# motordriver.net
KiCad netlist of a schematic drawn in Altium Designer
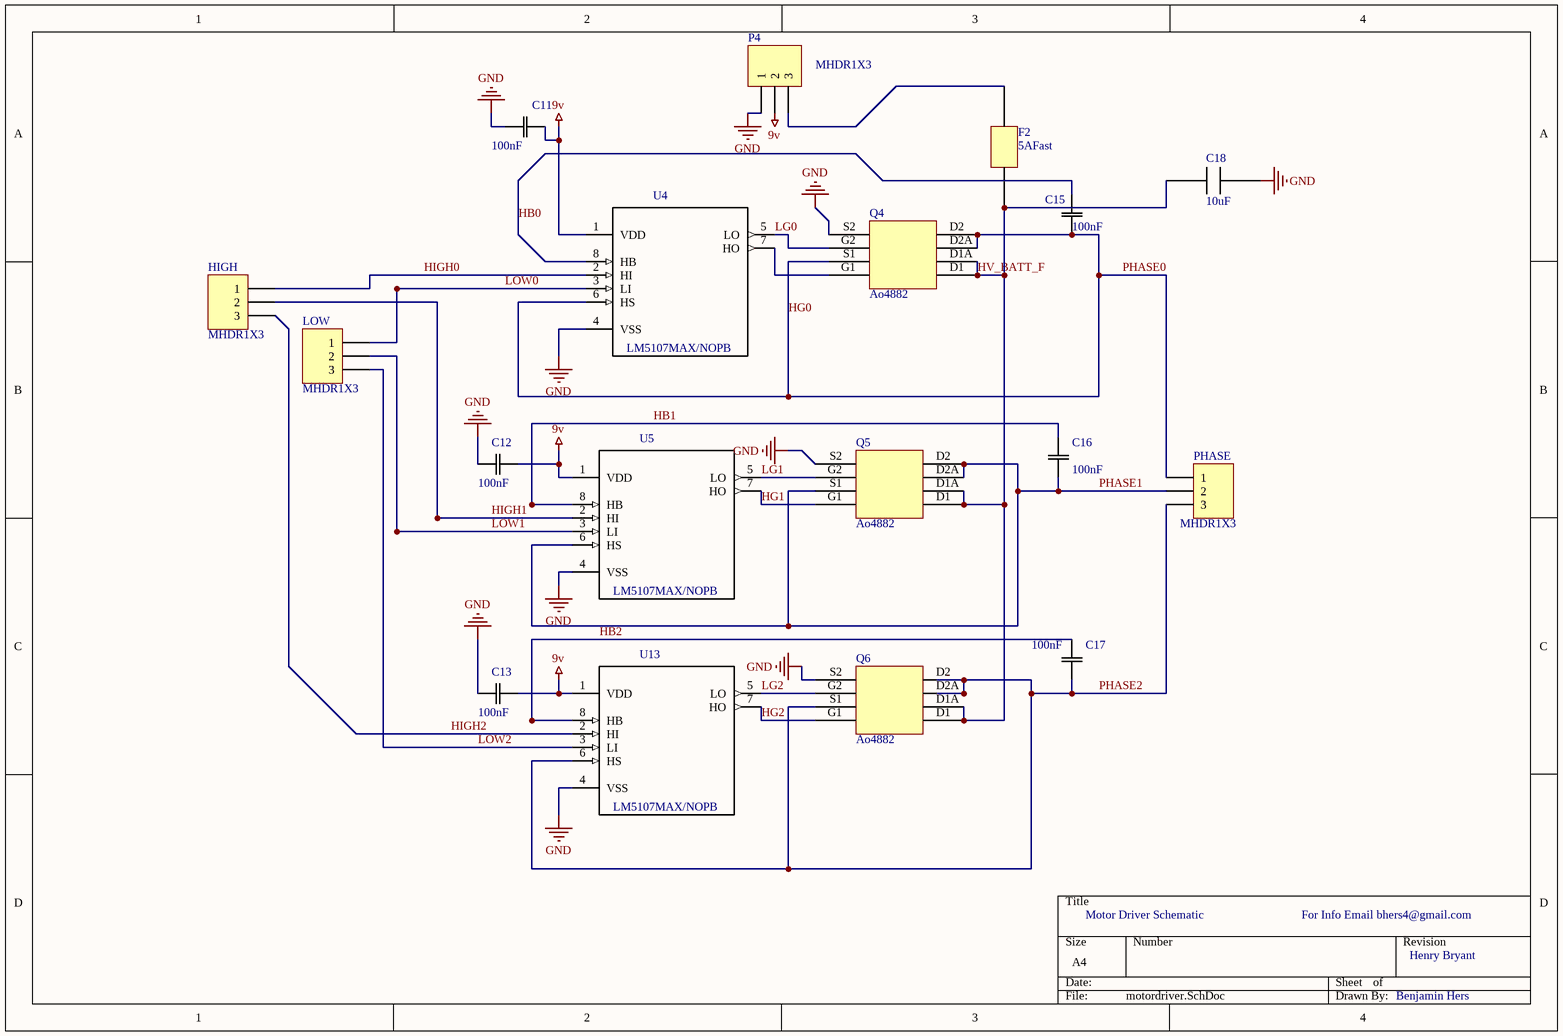
[diagram p0: motordriver.SchDoc]

(export (version "E")
  (design (tool "Eeschema 10.0.6"))
  (components
    (comp (ref "C11")
      (value "100nF")
      (footprint "CAPC2013X110N")
      (description "Capacitor; Ceramic; Cap; .100UF ; Tol+-10%; SMD; Vol-Rtg 50V; X7R, Tape/Reel")
      (fields (field (name "MP") "C0805C104K5RACTU") (field (name "MF") "Kemet"))
      (libsource (lib "100nF-C0805C104K5RACTU") (part "C0805C104K5RACTU"))
    )
    (comp (ref "C12")
      (value "100nF")
      (footprint "CAPC2013X110N")
      (description "Capacitor; Ceramic; Cap; .100UF ; Tol+-10%; SMD; Vol-Rtg 50V; X7R, Tape/Reel")
      (fields (field (name "MP") "C0805C104K5RACTU") (field (name "MF") "Kemet"))
      (libsource (lib "100nF-C0805C104K5RACTU") (part "C0805C104K5RACTU"))
    )
    (comp (ref "C13")
      (value "100nF")
      (footprint "CAPC2013X110N")
      (description "Capacitor; Ceramic; Cap; .100UF ; Tol+-10%; SMD; Vol-Rtg 50V; X7R, Tape/Reel")
      (fields (field (name "MP") "C0805C104K5RACTU") (field (name "MF") "Kemet"))
      (libsource (lib "100nF-C0805C104K5RACTU") (part "C0805C104K5RACTU"))
    )
    (comp (ref "C15")
      (value "100nF")
      (footprint "CAPC2013X110N")
      (description "Capacitor; Ceramic; Cap; .100UF ; Tol+-10%; SMD; Vol-Rtg 50V; X7R, Tape/Reel")
      (fields (field (name "MP") "C0805C104K5RACTU") (field (name "MF") "Kemet"))
      (libsource (lib "") (part "C0805C104K5RACTU_1"))
    )
    (comp (ref "C16")
      (value "100nF")
      (footprint "CAPC2013X110N")
      (description "Capacitor; Ceramic; Cap; .100UF ; Tol+-10%; SMD; Vol-Rtg 50V; X7R, Tape/Reel")
      (fields (field (name "MP") "C0805C104K5RACTU") (field (name "MF") "Kemet"))
      (libsource (lib "") (part "C0805C104K5RACTU_2"))
    )
    (comp (ref "C17")
      (value "100nF")
      (footprint "CAPC2013X110N")
      (description "Capacitor; Ceramic; Cap; .100UF ; Tol+-10%; SMD; Vol-Rtg 50V; X7R, Tape/Reel")
      (fields (field (name "MP") "C0805C104K5RACTU") (field (name "MF") "Kemet"))
      (libsource (lib "") (part "C0805C104K5RACTU_2"))
    )
    (comp (ref "C18")
      (value "10uF")
      (footprint "10uFCAPC3216X100N:CAPC3216X100N")
      (libsource (lib "altium-import") (part "root_0_Component_1_"))
    )
    (comp (ref "F2")
      (value "5AFast")
      (footprint "Fuse1206:1206")
      (libsource (lib "Fuse1206") (part "5AFast1206"))
    )
    (comp (ref "HIGH")
      (value "MHDR1X3")
      (footprint "MHDR1X3")
      (description "Header, 3-Pin")
      (fields (field (name "PUBLISHER") "Altium Limited"))
      (libsource (lib "") (part "MHDR1X3_1"))
    )
    (comp (ref "LOW")
      (value "MHDR1X3")
      (footprint "MHDR1X3")
      (description "Header, 3-Pin")
      (fields (field (name "PUBLISHER") "Altium Limited"))
      (libsource (lib "") (part "MHDR1X3_1"))
    )
    (comp (ref "P4")
      (value "MHDR1X3")
      (footprint "MHDR1X3")
      (description "Header, 3-Pin")
      (fields (field (name "PUBLISHER") "Altium Limited"))
      (libsource (lib "") (part "MHDR1X3_2"))
    )
    (comp (ref "PHASE")
      (value "MHDR1X3")
      (footprint "MHDR1X3")
      (description "Header, 3-Pin")
      (fields (field (name "PUBLISHER") "Altium Limited"))
      (libsource (lib "Miscellaneous Connectors") (part "MHDR1X3"))
    )
    (comp (ref "Q4")
      (value "Ao4882")
      (footprint "Ao4882:SOIC127P490X600X175-8N")
      (libsource (lib "Ao4882") (part "Ao4882"))
    )
    (comp (ref "Q5")
      (value "Ao4882")
      (footprint "Ao4882:SOIC127P490X600X175-8N")
      (libsource (lib "Ao4882") (part "Ao4882"))
    )
    (comp (ref "Q6")
      (value "Ao4882")
      (footprint "Ao4882:SOIC127P490X600X175-8N")
      (libsource (lib "Ao4882") (part "Ao4882"))
    )
    (comp (ref "U4")
      (value "LM5107MAX/NOPB")
      (footprint "LM5107MAX_NOPB:SOIC127P620X175-8N")
      (description "MOSFET DRVR 1.4A 2-OUT Hi/Lo Side Full Brdg/Half Brdg Non-Inv 8-Pin SOIC N T/R")
      (fields
        (field (name "DIGI-KEY_PART_NUMBER") "LM5107MAX/NOPBCT-ND")
        (field (name "MF") "Texas Instruments")
      )
      (libsource (lib "LM5107MAX_NOPB") (part "LM5107MAX/NOPB"))
    )
    (comp (ref "U5")
      (value "LM5107MAX/NOPB")
      (footprint "LM5107MAX_NOPB:SOIC127P620X175-8N")
      (description "MOSFET DRVR 1.4A 2-OUT Hi/Lo Side Full Brdg/Half Brdg Non-Inv 8-Pin SOIC N T/R")
      (fields
        (field (name "DIGI-KEY_PART_NUMBER") "LM5107MAX/NOPBCT-ND")
        (field (name "MF") "Texas Instruments")
      )
      (libsource (lib "LM5107MAX_NOPB") (part "LM5107MAX/NOPB"))
    )
    (comp (ref "U13")
      (value "LM5107MAX/NOPB")
      (footprint "LM5107MAX_NOPB:SOIC127P620X175-8N")
      (description "MOSFET DRVR 1.4A 2-OUT Hi/Lo Side Full Brdg/Half Brdg Non-Inv 8-Pin SOIC N T/R")
      (fields
        (field (name "DIGI-KEY_PART_NUMBER") "LM5107MAX/NOPBCT-ND")
        (field (name "MF") "Texas Instruments")
      )
      (libsource (lib "LM5107MAX_NOPB") (part "LM5107MAX/NOPB"))
    )
  )
  (nets
    (net (code "1") (name "/HB0") (class "Default")
      (node (ref "C15") (pin "2") (pinfunction "C2_2") (pintype "passive"))
      (node (ref "U4") (pin "8") (pinfunction "HB_8") (pintype "input"))
    )
    (net (code "2") (name "/HB1") (class "Default")
      (node (ref "C16") (pin "1") (pinfunction "C1_1") (pintype "passive"))
      (node (ref "U5") (pin "8") (pinfunction "HB_8") (pintype "input"))
    )
    (net (code "3") (name "/HB2") (class "Default")
      (node (ref "C17") (pin "1") (pinfunction "C1_1") (pintype "passive"))
      (node (ref "U13") (pin "8") (pinfunction "HB_8") (pintype "input"))
    )
    (net (code "4") (name "/HG0") (class "Default")
      (node (ref "C15") (pin "1") (pinfunction "C1_1") (pintype "passive"))
      (node (ref "PHASE") (pin "1") (pinfunction "1_1") (pintype "passive"))
      (node (ref "Q4") (pin "D2") (pinfunction "8_D2") (pintype "passive"))
      (node (ref "Q4") (pin "D2A") (pinfunction "7_D2A") (pintype "passive"))
      (node (ref "Q4") (pin "S1") (pinfunction "3_S1") (pintype "passive"))
      (node (ref "U4") (pin "6") (pinfunction "HS_6") (pintype "input"))
    )
    (net (code "5") (name "/HG1") (class "Default")
      (node (ref "Q5") (pin "G1") (pinfunction "4_G1") (pintype "passive"))
      (node (ref "U5") (pin "7") (pinfunction "HO_7") (pintype "output"))
    )
    (net (code "6") (name "/HG2") (class "Default")
      (node (ref "Q6") (pin "G1") (pinfunction "4_G1") (pintype "passive"))
      (node (ref "U13") (pin "7") (pinfunction "HO_7") (pintype "output"))
    )
    (net (code "7") (name "/HIGH0") (class "Default")
      (node (ref "HIGH") (pin "1") (pinfunction "1_1") (pintype "passive"))
      (node (ref "U4") (pin "2") (pinfunction "HI_2") (pintype "input"))
    )
    (net (code "8") (name "/HIGH1") (class "Default")
      (node (ref "HIGH") (pin "2") (pinfunction "2_2") (pintype "passive"))
      (node (ref "U5") (pin "2") (pinfunction "HI_2") (pintype "input"))
    )
    (net (code "9") (name "/HIGH2") (class "Default")
      (node (ref "HIGH") (pin "3") (pinfunction "3_3") (pintype "passive"))
      (node (ref "U13") (pin "2") (pinfunction "HI_2") (pintype "input"))
    )
    (net (code "10") (name "/HV_BATT_F") (class "Default")
      (node (ref "C18") (pin "In") (pinfunction "In_In") (pintype "passive"))
      (node (ref "F2") (pin "Fusein") (pinfunction "In_Fusein") (pintype "passive"))
      (node (ref "Q4") (pin "D1") (pinfunction "5_D1") (pintype "passive"))
      (node (ref "Q4") (pin "D1A") (pinfunction "6_D1A") (pintype "passive"))
      (node (ref "Q5") (pin "D1") (pinfunction "5_D1") (pintype "passive"))
      (node (ref "Q5") (pin "D1A") (pinfunction "6_D1A") (pintype "passive"))
      (node (ref "Q6") (pin "D1") (pinfunction "5_D1") (pintype "passive"))
      (node (ref "Q6") (pin "D1A") (pinfunction "6_D1A") (pintype "passive"))
    )
    (net (code "11") (name "/LG0") (class "Default")
      (node (ref "Q4") (pin "G2") (pinfunction "2_G2") (pintype "passive"))
      (node (ref "U4") (pin "5") (pinfunction "LO_5") (pintype "output"))
    )
    (net (code "12") (name "/LG1") (class "Default")
      (node (ref "Q5") (pin "G2") (pinfunction "2_G2") (pintype "passive"))
      (node (ref "U5") (pin "5") (pinfunction "LO_5") (pintype "output"))
    )
    (net (code "13") (name "/LG2") (class "Default")
      (node (ref "Q6") (pin "G2") (pinfunction "2_G2") (pintype "passive"))
      (node (ref "U13") (pin "5") (pinfunction "LO_5") (pintype "output"))
    )
    (net (code "14") (name "/LOW0") (class "Default")
      (node (ref "LOW") (pin "1") (pinfunction "1_1") (pintype "passive"))
      (node (ref "U4") (pin "3") (pinfunction "LI_3") (pintype "input"))
    )
    (net (code "15") (name "/LOW1") (class "Default")
      (node (ref "LOW") (pin "2") (pinfunction "2_2") (pintype "passive"))
      (node (ref "U5") (pin "3") (pinfunction "LI_3") (pintype "input"))
    )
    (net (code "16") (name "/LOW2") (class "Default")
      (node (ref "LOW") (pin "3") (pinfunction "3_3") (pintype "passive"))
      (node (ref "U13") (pin "3") (pinfunction "LI_3") (pintype "input"))
    )
    (net (code "17") (name "/PHASE1") (class "Default")
      (node (ref "C16") (pin "2") (pinfunction "C2_2") (pintype "passive"))
      (node (ref "PHASE") (pin "2") (pinfunction "2_2") (pintype "passive"))
      (node (ref "Q5") (pin "D2") (pinfunction "8_D2") (pintype "passive"))
      (node (ref "Q5") (pin "D2A") (pinfunction "7_D2A") (pintype "passive"))
      (node (ref "Q5") (pin "S1") (pinfunction "3_S1") (pintype "passive"))
      (node (ref "U5") (pin "6") (pinfunction "HS_6") (pintype "input"))
    )
    (net (code "18") (name "/PHASE2") (class "Default")
      (node (ref "C17") (pin "2") (pinfunction "C2_2") (pintype "passive"))
      (node (ref "PHASE") (pin "3") (pinfunction "3_3") (pintype "passive"))
      (node (ref "Q6") (pin "D2") (pinfunction "8_D2") (pintype "passive"))
      (node (ref "Q6") (pin "D2A") (pinfunction "7_D2A") (pintype "passive"))
      (node (ref "Q6") (pin "S1") (pinfunction "3_S1") (pintype "passive"))
      (node (ref "U13") (pin "6") (pinfunction "HS_6") (pintype "input"))
    )
    (net (code "19") (name "9v") (class "Default")
      (node (ref "C11") (pin "1") (pinfunction "C1_1") (pintype "passive"))
      (node (ref "C12") (pin "2") (pinfunction "C2_2") (pintype "passive"))
      (node (ref "C13") (pin "2") (pinfunction "C2_2") (pintype "passive"))
      (node (ref "P4") (pin "2") (pinfunction "2_2") (pintype "passive"))
      (node (ref "U13") (pin "1") (pinfunction "VDD_1") (pintype "power_in"))
      (node (ref "U4") (pin "1") (pinfunction "VDD_1") (pintype "power_in"))
      (node (ref "U5") (pin "1") (pinfunction "VDD_1") (pintype "power_in"))
    )
    (net (code "20") (name "GND") (class "Default")
      (node (ref "C11") (pin "2") (pinfunction "C2_2") (pintype "passive"))
      (node (ref "C12") (pin "1") (pinfunction "C1_1") (pintype "passive"))
      (node (ref "C13") (pin "1") (pinfunction "C1_1") (pintype "passive"))
      (node (ref "C18") (pin "Out") (pinfunction "Out_Out") (pintype "passive"))
      (node (ref "P4") (pin "1") (pinfunction "1_1") (pintype "passive"))
      (node (ref "Q4") (pin "S2") (pinfunction "1_S2") (pintype "passive"))
      (node (ref "Q5") (pin "S2") (pinfunction "1_S2") (pintype "passive"))
      (node (ref "Q6") (pin "S2") (pinfunction "1_S2") (pintype "passive"))
      (node (ref "U13") (pin "4") (pinfunction "VSS_4") (pintype "power_in"))
      (node (ref "U4") (pin "4") (pinfunction "VSS_4") (pintype "power_in"))
      (node (ref "U5") (pin "4") (pinfunction "VSS_4") (pintype "power_in"))
    )
    (net (code "21") (name "Net-(F2-Out)") (class "Default")
      (node (ref "F2") (pin "Fuseout") (pinfunction "Out_Fuseout") (pintype "passive"))
      (node (ref "P4") (pin "3") (pinfunction "3_3") (pintype "passive"))
    )
    (net (code "22") (name "Net-(Q4-4)") (class "Default")
      (node (ref "Q4") (pin "G1") (pinfunction "4_G1") (pintype "passive"))
      (node (ref "U4") (pin "7") (pinfunction "HO_7") (pintype "output"))
    )
  )
)
